# MCU.net
KiCad netlist of a schematic drawn in Altium Designer
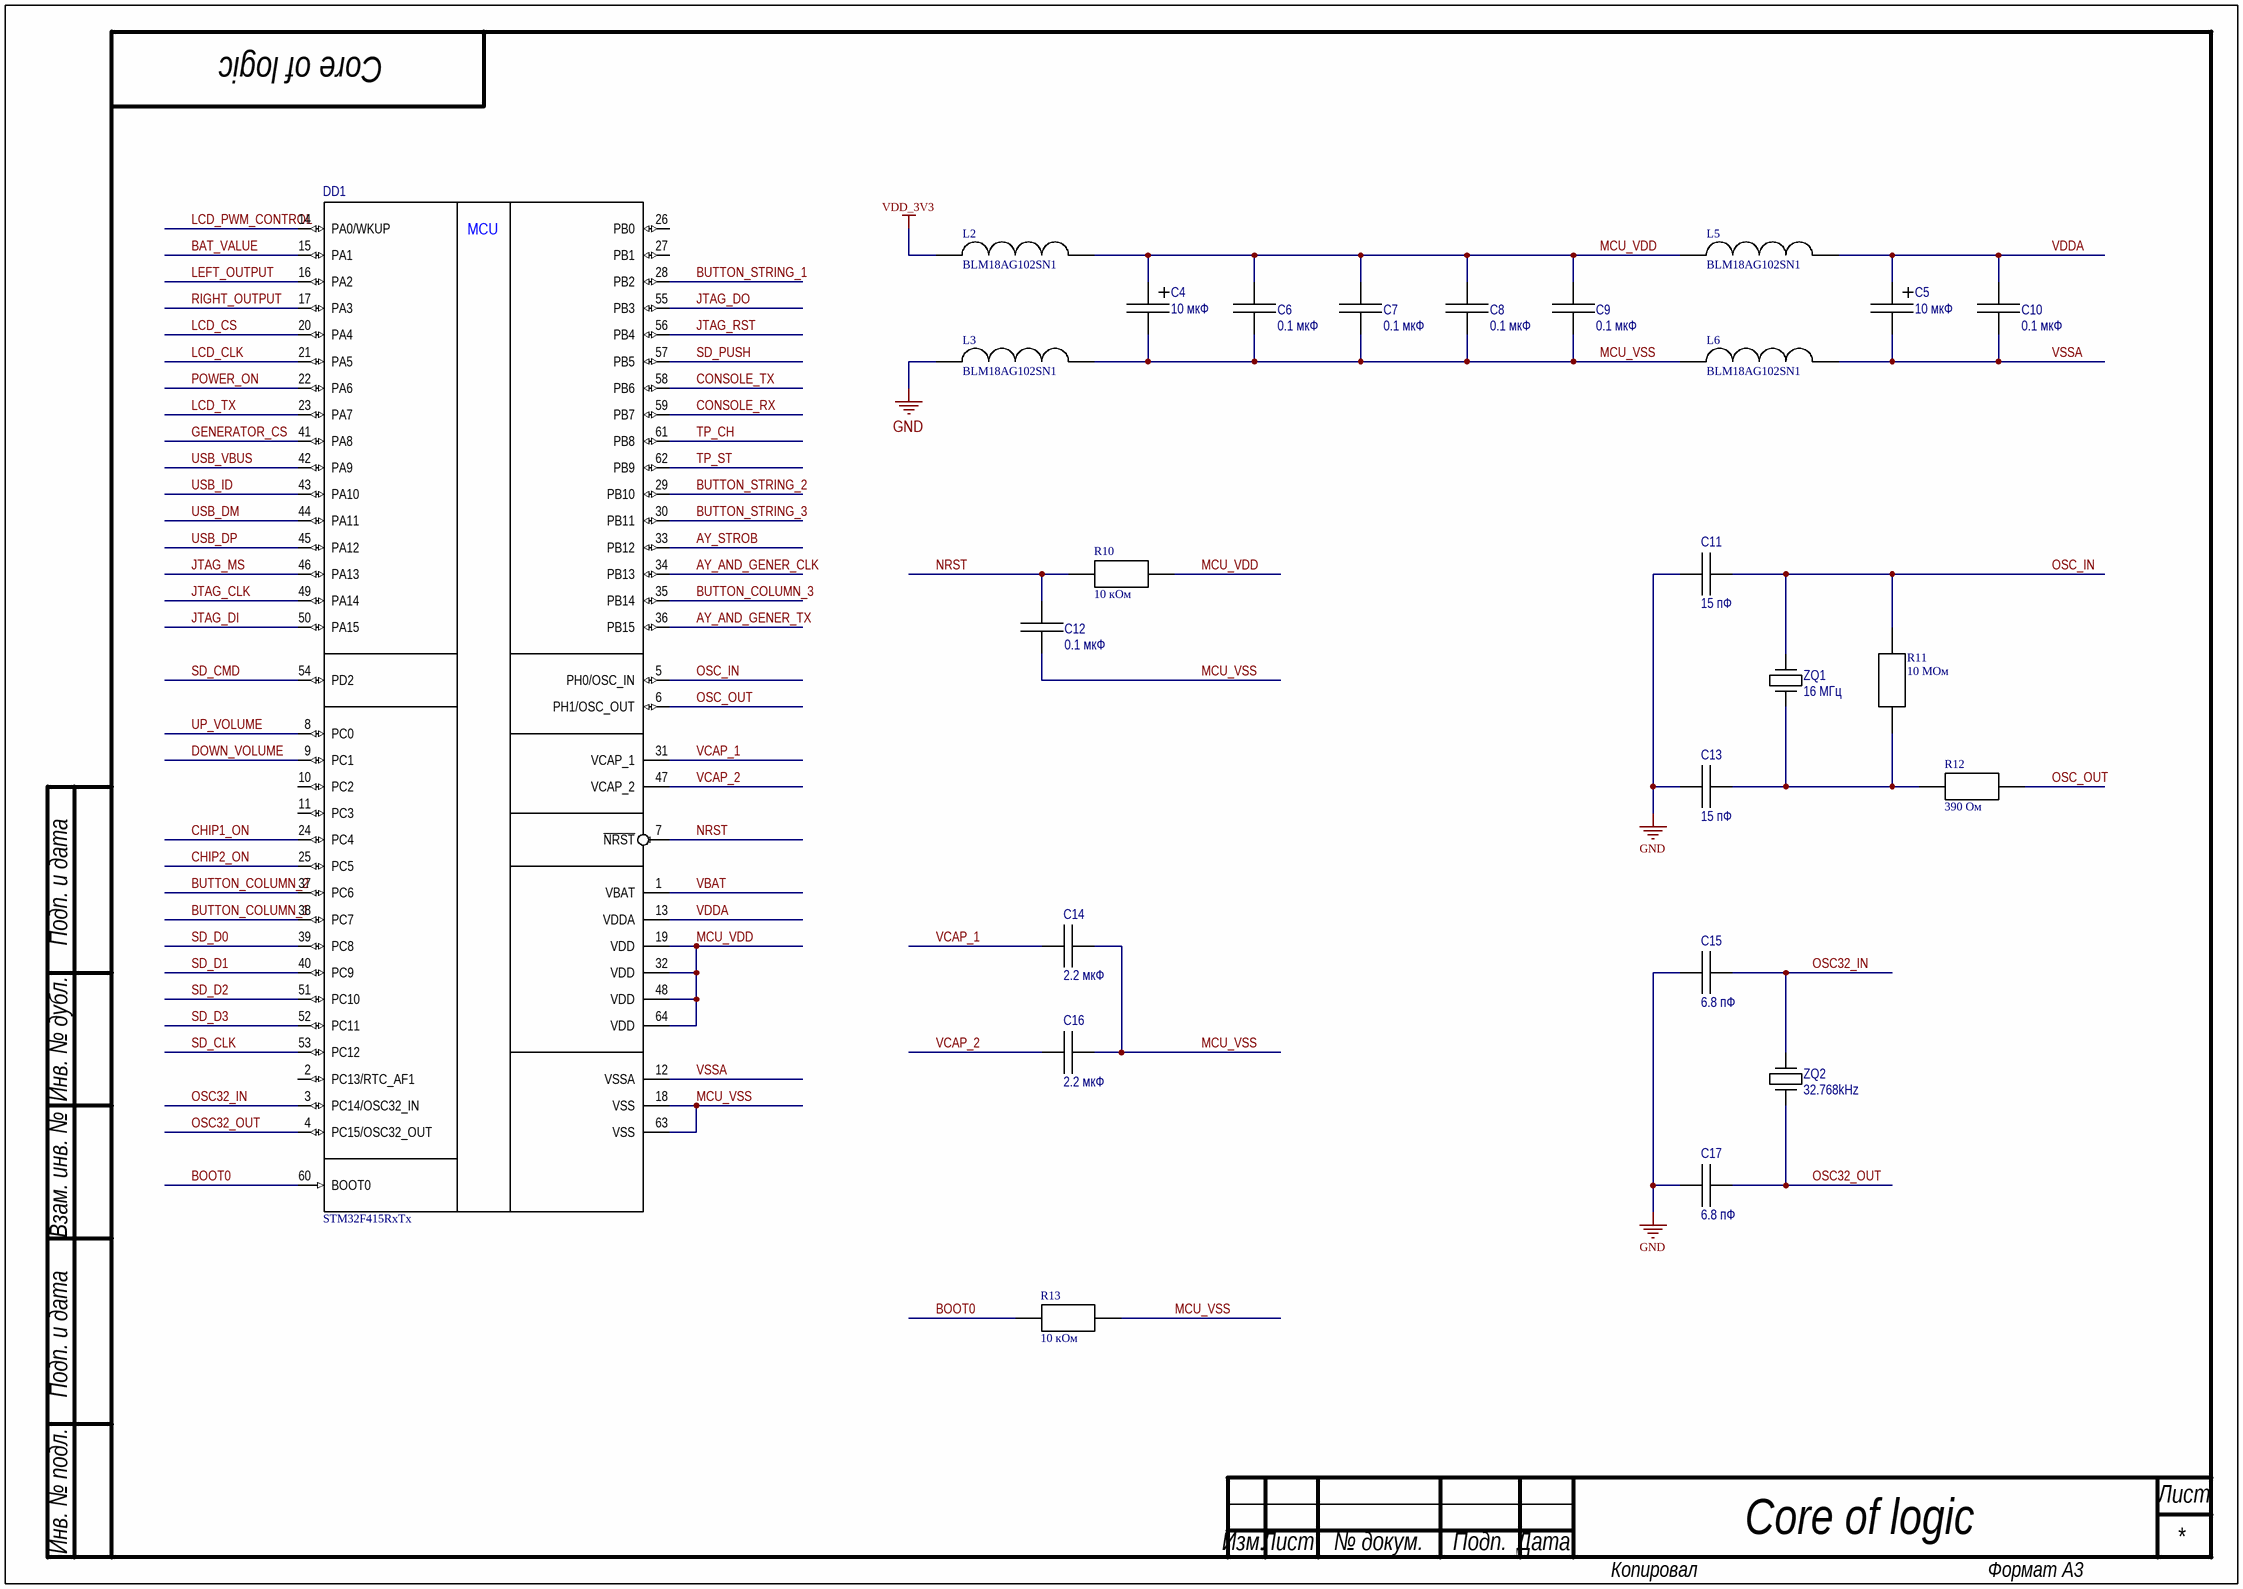
[diagram p0: MCU.SchDoc]

(export (version "E")
  (design (tool "Eeschema 10.0.6"))
  (components
    (comp (ref "C4")
      (value "10 мкФ")
      (footprint "C TAN_A")
      (description "SMD Tantalium Capacitor A")
      (libsource (lib "my_lib") (part "CAP TAN_A"))
    )
    (comp (ref "C5")
      (value "10 мкФ")
      (footprint "C TAN_A")
      (description "SMD Tantalium Capacitor A")
      (libsource (lib "my_lib") (part "CAP TAN_A"))
    )
    (comp (ref "C6")
      (value "0.1 мкФ")
      (footprint "C 0805")
      (description "SMD Capacitor 0805")
      (libsource (lib "my_lib") (part "CAP 0805"))
    )
    (comp (ref "C7")
      (value "0.1 мкФ")
      (footprint "C 0805")
      (description "SMD Capacitor 0805")
      (libsource (lib "my_lib") (part "CAP 0805"))
    )
    (comp (ref "C8")
      (value "0.1 мкФ")
      (footprint "C 0805")
      (description "SMD Capacitor 0805")
      (libsource (lib "my_lib") (part "CAP 0805"))
    )
    (comp (ref "C9")
      (value "0.1 мкФ")
      (footprint "C 0805")
      (description "SMD Capacitor 0805")
      (libsource (lib "my_lib") (part "CAP 0805"))
    )
    (comp (ref "C10")
      (value "0.1 мкФ")
      (footprint "C 0805")
      (description "SMD Capacitor 0805")
      (libsource (lib "my_lib") (part "CAP 0805"))
    )
    (comp (ref "C11")
      (value "15 пФ")
      (footprint "C 0805")
      (description "SMD Capacitor 0805")
      (libsource (lib "my_lib") (part "CAP 0805"))
    )
    (comp (ref "C12")
      (value "0.1 мкФ")
      (footprint "C 0805")
      (description "SMD Capacitor 0805")
      (libsource (lib "my_lib") (part "CAP 0805"))
    )
    (comp (ref "C13")
      (value "15 пФ")
      (footprint "C 0805")
      (description "SMD Capacitor 0805")
      (libsource (lib "my_lib") (part "CAP 0805"))
    )
    (comp (ref "C14")
      (value "2.2 мкФ")
      (footprint "C 0805")
      (description "SMD Capacitor 0805")
      (libsource (lib "my_lib") (part "CAP 0805"))
    )
    (comp (ref "C15")
      (value "6.8 пФ")
      (footprint "C 0805")
      (description "SMD Capacitor 0805")
      (libsource (lib "my_lib") (part "CAP 0805"))
    )
    (comp (ref "C16")
      (value "2.2 мкФ")
      (footprint "C 0805")
      (description "SMD Capacitor 0805")
      (libsource (lib "my_lib") (part "CAP 0805"))
    )
    (comp (ref "C17")
      (value "6.8 пФ")
      (footprint "C 0805")
      (description "SMD Capacitor 0805")
      (libsource (lib "my_lib") (part "CAP 0805"))
    )
    (comp (ref "DD1")
      (value "STM32F415RxTx")
      (footprint "LQFP64")
      (libsource (lib "my_lib") (part "STM32F415RxTx"))
    )
    (comp (ref "L2")
      (value "BLM18AG102SN1")
      (footprint "FB 0603")
      (libsource (lib "my_lib") (part "BLM18AG102SN1"))
    )
    (comp (ref "L3")
      (value "BLM18AG102SN1")
      (footprint "FB 0603")
      (libsource (lib "my_lib") (part "BLM18AG102SN1"))
    )
    (comp (ref "L5")
      (value "BLM18AG102SN1")
      (footprint "FB 0603")
      (libsource (lib "my_lib") (part "BLM18AG102SN1"))
    )
    (comp (ref "L6")
      (value "BLM18AG102SN1")
      (footprint "FB 0603")
      (libsource (lib "my_lib") (part "BLM18AG102SN1"))
    )
    (comp (ref "R10") (value "10 кОм") (footprint "RES 0402") (libsource (lib "my_lib") (part "RES 0402")))
    (comp (ref "R11") (value "10 МОм") (footprint "RES 0402") (libsource (lib "my_lib") (part "RES 0402")))
    (comp (ref "R12") (value "390 Ом") (footprint "RES 0402") (libsource (lib "my_lib") (part "RES 0402")))
    (comp (ref "R13") (value "10 кОм") (footprint "RES 0402") (libsource (lib "my_lib") (part "RES 0402")))
    (comp (ref "ZQ1")
      (value "16 МГц")
      (footprint "NX3225SA")
      (description "QUARTZ CRYSTAL")
      (fields (field (name "MANUFACTURER") "NDK") (field (name "Comment") "NX3225SA-16.000M-STD-CRS-2"))
      (libsource (lib "my_lib") (part "NX3225SA-16.000M-STD-CRS-2"))
    )
    (comp (ref "ZQ2")
      (value "32.768kHz")
      (footprint "MC-306")
      (description "QUARTZ CRYSTAL")
      (fields (field (name "Comment") "MC-306"))
      (libsource (lib "my_lib") (part "MC-306"))
    )
  )
  (nets
    (net (code "1") (name "/AY_AND_GENER_CLK") (class "Default")
      (node (ref "DD1") (pin "34") (pinfunction "PB13_34") (pintype "bidirectional"))
    )
    (net (code "2") (name "/AY_AND_GENER_TX") (class "Default")
      (node (ref "DD1") (pin "36") (pinfunction "PB15_36") (pintype "bidirectional"))
    )
    (net (code "3") (name "/AY_STROB") (class "Default")
      (node (ref "DD1") (pin "33") (pinfunction "PB12_33") (pintype "bidirectional"))
    )
    (net (code "4") (name "/BAT_VALUE") (class "Default")
      (node (ref "DD1") (pin "15") (pinfunction "PA1_15") (pintype "bidirectional"))
    )
    (net (code "5") (name "/BOOT0") (class "Default")
      (node (ref "DD1") (pin "60") (pinfunction "BOOT0_60") (pintype "input"))
      (node (ref "R13") (pin "1") (pinfunction "1_1") (pintype "passive"))
    )
    (net (code "6") (name "/BUTTON_COLUMN_1") (class "Default")
      (node (ref "DD1") (pin "38") (pinfunction "PC7_38") (pintype "bidirectional"))
    )
    (net (code "7") (name "/BUTTON_COLUMN_2") (class "Default")
      (node (ref "DD1") (pin "37") (pinfunction "PC6_37") (pintype "bidirectional"))
    )
    (net (code "8") (name "/BUTTON_COLUMN_3") (class "Default")
      (node (ref "DD1") (pin "35") (pinfunction "PB14_35") (pintype "bidirectional"))
    )
    (net (code "9") (name "/BUTTON_STRING_1") (class "Default")
      (node (ref "DD1") (pin "28") (pinfunction "PB2_28") (pintype "bidirectional"))
    )
    (net (code "10") (name "/BUTTON_STRING_2") (class "Default")
      (node (ref "DD1") (pin "29") (pinfunction "PB10_29") (pintype "bidirectional"))
    )
    (net (code "11") (name "/BUTTON_STRING_3") (class "Default")
      (node (ref "DD1") (pin "30") (pinfunction "PB11_30") (pintype "bidirectional"))
    )
    (net (code "12") (name "/CHIP1_ON") (class "Default")
      (node (ref "DD1") (pin "24") (pinfunction "PC4_24") (pintype "bidirectional"))
    )
    (net (code "13") (name "/CHIP2_ON") (class "Default")
      (node (ref "DD1") (pin "25") (pinfunction "PC5_25") (pintype "bidirectional"))
    )
    (net (code "14") (name "/CONSOLE_RX") (class "Default")
      (node (ref "DD1") (pin "59") (pinfunction "PB7_59") (pintype "bidirectional"))
    )
    (net (code "15") (name "/CONSOLE_TX") (class "Default")
      (node (ref "DD1") (pin "58") (pinfunction "PB6_58") (pintype "bidirectional"))
    )
    (net (code "16") (name "/DOWN_VOLUME") (class "Default")
      (node (ref "DD1") (pin "9") (pinfunction "PC1_9") (pintype "bidirectional"))
    )
    (net (code "17") (name "/GENERATOR_CS") (class "Default")
      (node (ref "DD1") (pin "41") (pinfunction "PA8_41") (pintype "bidirectional"))
    )
    (net (code "18") (name "/JTAG_CLK") (class "Default")
      (node (ref "DD1") (pin "49") (pinfunction "PA14_49") (pintype "bidirectional"))
    )
    (net (code "19") (name "/JTAG_DI") (class "Default")
      (node (ref "DD1") (pin "50") (pinfunction "PA15_50") (pintype "bidirectional"))
    )
    (net (code "20") (name "/JTAG_DO") (class "Default")
      (node (ref "DD1") (pin "55") (pinfunction "PB3_55") (pintype "bidirectional"))
    )
    (net (code "21") (name "/JTAG_MS") (class "Default")
      (node (ref "DD1") (pin "46") (pinfunction "PA13_46") (pintype "bidirectional"))
    )
    (net (code "22") (name "/JTAG_RST") (class "Default")
      (node (ref "DD1") (pin "56") (pinfunction "PB4_56") (pintype "bidirectional"))
    )
    (net (code "23") (name "/LCD_CLK") (class "Default")
      (node (ref "DD1") (pin "21") (pinfunction "PA5_21") (pintype "bidirectional"))
    )
    (net (code "24") (name "/LCD_CS") (class "Default")
      (node (ref "DD1") (pin "20") (pinfunction "PA4_20") (pintype "bidirectional"))
    )
    (net (code "25") (name "/LCD_PWM_CONTROL") (class "Default")
      (node (ref "DD1") (pin "14") (pinfunction "PA0/WKUP_14") (pintype "bidirectional"))
    )
    (net (code "26") (name "/LCD_TX") (class "Default")
      (node (ref "DD1") (pin "23") (pinfunction "PA7_23") (pintype "bidirectional"))
    )
    (net (code "27") (name "/LEFT_OUTPUT") (class "Default")
      (node (ref "DD1") (pin "16") (pinfunction "PA2_16") (pintype "bidirectional"))
    )
    (net (code "28") (name "/MCU_VDD") (class "Default")
      (node (ref "C4") (pin "1") (pinfunction "1_1") (pintype "passive"))
      (node (ref "C6") (pin "2") (pinfunction "2_2") (pintype "passive"))
      (node (ref "C7") (pin "2") (pinfunction "2_2") (pintype "passive"))
      (node (ref "C8") (pin "2") (pinfunction "2_2") (pintype "passive"))
      (node (ref "C9") (pin "2") (pinfunction "2_2") (pintype "passive"))
      (node (ref "DD1") (pin "19") (pinfunction "VDD_19") (pintype "power_in"))
      (node (ref "DD1") (pin "32") (pinfunction "VDD_32") (pintype "power_in"))
      (node (ref "DD1") (pin "48") (pinfunction "VDD_48") (pintype "power_in"))
      (node (ref "DD1") (pin "64") (pinfunction "VDD_64") (pintype "power_in"))
      (node (ref "L2") (pin "2") (pinfunction "2_2") (pintype "passive"))
      (node (ref "L5") (pin "1") (pinfunction "1_1") (pintype "passive"))
      (node (ref "R10") (pin "2") (pinfunction "2_2") (pintype "passive"))
    )
    (net (code "29") (name "/MCU_VSS") (class "Default")
      (node (ref "C12") (pin "1") (pinfunction "1_1") (pintype "passive"))
      (node (ref "C14") (pin "2") (pinfunction "2_2") (pintype "passive"))
      (node (ref "C16") (pin "2") (pinfunction "2_2") (pintype "passive"))
      (node (ref "C4") (pin "2") (pinfunction "2_2") (pintype "passive"))
      (node (ref "C6") (pin "1") (pinfunction "1_1") (pintype "passive"))
      (node (ref "C7") (pin "1") (pinfunction "1_1") (pintype "passive"))
      (node (ref "C8") (pin "1") (pinfunction "1_1") (pintype "passive"))
      (node (ref "C9") (pin "1") (pinfunction "1_1") (pintype "passive"))
      (node (ref "DD1") (pin "18") (pinfunction "VSS_18") (pintype "power_in"))
      (node (ref "DD1") (pin "63") (pinfunction "VSS_63") (pintype "power_in"))
      (node (ref "L3") (pin "2") (pinfunction "2_2") (pintype "passive"))
      (node (ref "L6") (pin "1") (pinfunction "1_1") (pintype "passive"))
      (node (ref "R13") (pin "2") (pinfunction "2_2") (pintype "passive"))
    )
    (net (code "30") (name "/NRST") (class "Default")
      (node (ref "C12") (pin "2") (pinfunction "2_2") (pintype "passive"))
      (node (ref "DD1") (pin "7") (pinfunction "~{NRST}_7") (pintype "input"))
      (node (ref "R10") (pin "1") (pinfunction "1_1") (pintype "passive"))
    )
    (net (code "31") (name "/OSC32_IN") (class "Default")
      (node (ref "C15") (pin "1") (pinfunction "1_1") (pintype "passive"))
      (node (ref "DD1") (pin "3") (pinfunction "PC14/OSC32_IN_3") (pintype "bidirectional"))
      (node (ref "ZQ2") (pin "4") (pinfunction "XO_4") (pintype "passive"))
    )
    (net (code "32") (name "/OSC32_OUT") (class "Default")
      (node (ref "C17") (pin "1") (pinfunction "1_1") (pintype "passive"))
      (node (ref "DD1") (pin "4") (pinfunction "PC15/OSC32_OUT_4") (pintype "bidirectional"))
      (node (ref "ZQ2") (pin "1") (pinfunction "XI_1") (pintype "passive"))
    )
    (net (code "33") (name "/OSC_IN") (class "Default")
      (node (ref "C11") (pin "1") (pinfunction "1_1") (pintype "passive"))
      (node (ref "DD1") (pin "5") (pinfunction "PH0/OSC_IN_5") (pintype "bidirectional"))
      (node (ref "R11") (pin "2") (pinfunction "2_2") (pintype "passive"))
      (node (ref "ZQ1") (pin "3") (pinfunction "XO_3") (pintype "passive"))
    )
    (net (code "34") (name "/OSC_OUT") (class "Default")
      (node (ref "DD1") (pin "6") (pinfunction "PH1/OSC_OUT_6") (pintype "bidirectional"))
      (node (ref "R12") (pin "1") (pinfunction "1_1") (pintype "passive"))
    )
    (net (code "35") (name "/POWER_ON") (class "Default")
      (node (ref "DD1") (pin "22") (pinfunction "PA6_22") (pintype "bidirectional"))
    )
    (net (code "36") (name "/RIGHT_OUTPUT") (class "Default")
      (node (ref "DD1") (pin "17") (pinfunction "PA3_17") (pintype "bidirectional"))
    )
    (net (code "37") (name "/SD_CLK") (class "Default")
      (node (ref "DD1") (pin "53") (pinfunction "PC12_53") (pintype "bidirectional"))
    )
    (net (code "38") (name "/SD_CMD") (class "Default")
      (node (ref "DD1") (pin "54") (pinfunction "PD2_54") (pintype "bidirectional"))
    )
    (net (code "39") (name "/SD_D0") (class "Default")
      (node (ref "DD1") (pin "39") (pinfunction "PC8_39") (pintype "bidirectional"))
    )
    (net (code "40") (name "/SD_D1") (class "Default")
      (node (ref "DD1") (pin "40") (pinfunction "PC9_40") (pintype "bidirectional"))
    )
    (net (code "41") (name "/SD_D2") (class "Default")
      (node (ref "DD1") (pin "51") (pinfunction "PC10_51") (pintype "bidirectional"))
    )
    (net (code "42") (name "/SD_D3") (class "Default")
      (node (ref "DD1") (pin "52") (pinfunction "PC11_52") (pintype "bidirectional"))
    )
    (net (code "43") (name "/SD_PUSH") (class "Default")
      (node (ref "DD1") (pin "57") (pinfunction "PB5_57") (pintype "bidirectional"))
    )
    (net (code "44") (name "/TP_CH") (class "Default")
      (node (ref "DD1") (pin "61") (pinfunction "PB8_61") (pintype "bidirectional"))
    )
    (net (code "45") (name "/TP_ST") (class "Default")
      (node (ref "DD1") (pin "62") (pinfunction "PB9_62") (pintype "bidirectional"))
    )
    (net (code "46") (name "/UP_VOLUME") (class "Default")
      (node (ref "DD1") (pin "8") (pinfunction "PC0_8") (pintype "bidirectional"))
    )
    (net (code "47") (name "/USB_DM") (class "Default")
      (node (ref "DD1") (pin "44") (pinfunction "PA11_44") (pintype "bidirectional"))
    )
    (net (code "48") (name "/USB_DP") (class "Default")
      (node (ref "DD1") (pin "45") (pinfunction "PA12_45") (pintype "bidirectional"))
    )
    (net (code "49") (name "/USB_ID") (class "Default")
      (node (ref "DD1") (pin "43") (pinfunction "PA10_43") (pintype "bidirectional"))
    )
    (net (code "50") (name "/USB_VBUS") (class "Default")
      (node (ref "DD1") (pin "42") (pinfunction "PA9_42") (pintype "bidirectional"))
    )
    (net (code "51") (name "/VBAT") (class "Default")
      (node (ref "DD1") (pin "1") (pinfunction "VBAT_1") (pintype "power_in"))
    )
    (net (code "52") (name "/VCAP_1") (class "Default")
      (node (ref "C14") (pin "1") (pinfunction "1_1") (pintype "passive"))
      (node (ref "DD1") (pin "31") (pinfunction "VCAP_1_31") (pintype "power_in"))
    )
    (net (code "53") (name "/VCAP_2") (class "Default")
      (node (ref "C16") (pin "1") (pinfunction "1_1") (pintype "passive"))
      (node (ref "DD1") (pin "47") (pinfunction "VCAP_2_47") (pintype "power_in"))
    )
    (net (code "54") (name "/VDDA") (class "Default")
      (node (ref "C10") (pin "2") (pinfunction "2_2") (pintype "passive"))
      (node (ref "C5") (pin "1") (pinfunction "1_1") (pintype "passive"))
      (node (ref "DD1") (pin "13") (pinfunction "VDDA_13") (pintype "power_in"))
      (node (ref "L5") (pin "2") (pinfunction "2_2") (pintype "passive"))
    )
    (net (code "55") (name "/VSSA") (class "Default")
      (node (ref "C10") (pin "1") (pinfunction "1_1") (pintype "passive"))
      (node (ref "C5") (pin "2") (pinfunction "2_2") (pintype "passive"))
      (node (ref "DD1") (pin "12") (pinfunction "VSSA_12") (pintype "power_in"))
      (node (ref "L6") (pin "2") (pinfunction "2_2") (pintype "passive"))
    )
    (net (code "56") (name "GND") (class "Default")
      (node (ref "C11") (pin "2") (pinfunction "2_2") (pintype "passive"))
      (node (ref "C13") (pin "2") (pinfunction "2_2") (pintype "passive"))
      (node (ref "C15") (pin "2") (pinfunction "2_2") (pintype "passive"))
      (node (ref "C17") (pin "2") (pinfunction "2_2") (pintype "passive"))
      (node (ref "L3") (pin "1") (pinfunction "1_1") (pintype "passive"))
    )
    (net (code "57") (name "Net-(ZQ1-XI)") (class "Default")
      (node (ref "C13") (pin "1") (pinfunction "1_1") (pintype "passive"))
      (node (ref "R11") (pin "1") (pinfunction "1_1") (pintype "passive"))
      (node (ref "R12") (pin "2") (pinfunction "2_2") (pintype "passive"))
      (node (ref "ZQ1") (pin "1") (pinfunction "XI_1") (pintype "passive"))
    )
    (net (code "58") (name "VDD_3V3") (class "Default")
      (node (ref "L2") (pin "1") (pinfunction "1_1") (pintype "passive"))
    )
    (net (code "59") (name "unconnected-(DD1-PB0-Pad26)") (class "Default")
      (node (ref "DD1") (pin "26") (pinfunction "PB0_26") (pintype "bidirectional"))
    )
    (net (code "60") (name "unconnected-(DD1-PB1-Pad27)") (class "Default")
      (node (ref "DD1") (pin "27") (pinfunction "PB1_27") (pintype "bidirectional"))
    )
    (net (code "61") (name "unconnected-(DD1-PC2-Pad10)") (class "Default")
      (node (ref "DD1") (pin "10") (pinfunction "PC2_10") (pintype "bidirectional"))
    )
    (net (code "62") (name "unconnected-(DD1-PC3-Pad11)") (class "Default")
      (node (ref "DD1") (pin "11") (pinfunction "PC3_11") (pintype "bidirectional"))
    )
    (net (code "63") (name "unconnected-(DD1-PC13{slash}RTC_AF1-Pad2)") (class "Default")
      (node (ref "DD1") (pin "2") (pinfunction "PC13/RTC_AF1_2") (pintype "bidirectional"))
    )
    (net (code "64") (name "unconnected-(ZQ1-NC-Pad2)") (class "Default")
      (node (ref "ZQ1") (pin "2") (pinfunction "NC_2") (pintype "passive"))
    )
    (net (code "65") (name "unconnected-(ZQ1-NC-Pad4)") (class "Default")
      (node (ref "ZQ1") (pin "4") (pinfunction "NC_4") (pintype "passive"))
    )
    (net (code "66") (name "unconnected-(ZQ2-NC-Pad2)") (class "Default")
      (node (ref "ZQ2") (pin "2") (pinfunction "NC_2") (pintype "passive"))
    )
    (net (code "67") (name "unconnected-(ZQ2-NC-Pad4)") (class "Default")
      (node (ref "ZQ2") (pin "4") (pinfunction "NC_4") (pintype "passive"))
    )
  )
)
